# Probe4RackV1_1.net
KiCad netlist of a schematic drawn in Altium Designer
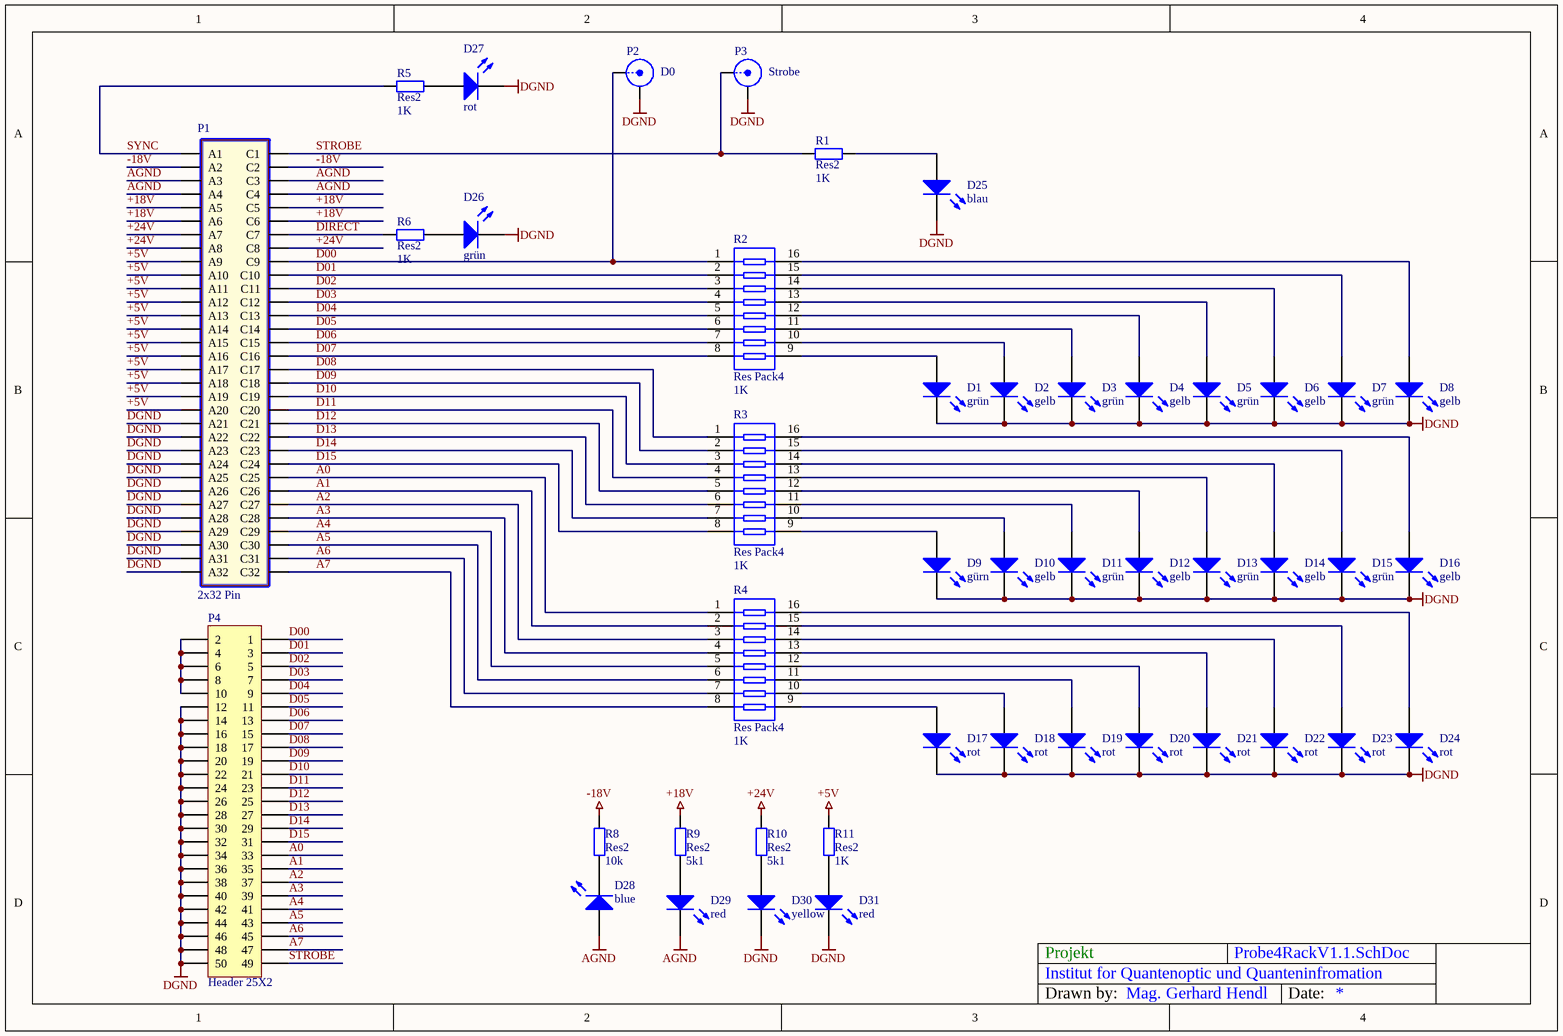
[diagram p0: Probe4RackV1.1.SchDoc]

(export (version "E")
  (design (tool "Eeschema 10.0.6"))
  (components
    (comp (ref "D1")
      (value "grün")
      (footprint "3.2X1.6X1.1")
      (description "Typical BLUE SiC LED")
      (fields (field (name "PUBLISHER") "Altium Limited"))
      (libsource (lib "Miscellaneous Devices") (part "LED3"))
    )
    (comp (ref "D2")
      (value "gelb")
      (footprint "3.2X1.6X1.1")
      (description "Typical BLUE SiC LED")
      (fields (field (name "PUBLISHER") "Altium Limited"))
      (libsource (lib "Miscellaneous Devices") (part "LED3"))
    )
    (comp (ref "D3")
      (value "grün")
      (footprint "3.2X1.6X1.1")
      (description "Typical BLUE SiC LED")
      (fields (field (name "PUBLISHER") "Altium Limited"))
      (libsource (lib "Miscellaneous Devices") (part "LED3"))
    )
    (comp (ref "D4")
      (value "gelb")
      (footprint "3.2X1.6X1.1")
      (description "Typical BLUE SiC LED")
      (fields (field (name "PUBLISHER") "Altium Limited"))
      (libsource (lib "Miscellaneous Devices") (part "LED3"))
    )
    (comp (ref "D5")
      (value "grün")
      (footprint "3.2X1.6X1.1")
      (description "Typical BLUE SiC LED")
      (fields (field (name "PUBLISHER") "Altium Limited"))
      (libsource (lib "Miscellaneous Devices") (part "LED3"))
    )
    (comp (ref "D6")
      (value "gelb")
      (footprint "3.2X1.6X1.1")
      (description "Typical BLUE SiC LED")
      (fields (field (name "PUBLISHER") "Altium Limited"))
      (libsource (lib "Miscellaneous Devices") (part "LED3"))
    )
    (comp (ref "D7")
      (value "grün")
      (footprint "3.2X1.6X1.1")
      (description "Typical BLUE SiC LED")
      (fields (field (name "PUBLISHER") "Altium Limited"))
      (libsource (lib "Miscellaneous Devices") (part "LED3"))
    )
    (comp (ref "D8")
      (value "gelb")
      (footprint "3.2X1.6X1.1")
      (description "Typical BLUE SiC LED")
      (fields (field (name "PUBLISHER") "Altium Limited"))
      (libsource (lib "Miscellaneous Devices") (part "LED3"))
    )
    (comp (ref "D9")
      (value "gürn")
      (footprint "3.2X1.6X1.1")
      (description "Typical BLUE SiC LED")
      (fields (field (name "PUBLISHER") "Altium Limited"))
      (libsource (lib "Miscellaneous Devices") (part "LED3"))
    )
    (comp (ref "D10")
      (value "gelb")
      (footprint "3.2X1.6X1.1")
      (description "Typical BLUE SiC LED")
      (fields (field (name "PUBLISHER") "Altium Limited"))
      (libsource (lib "Miscellaneous Devices") (part "LED3"))
    )
    (comp (ref "D11")
      (value "grün")
      (footprint "3.2X1.6X1.1")
      (description "Typical BLUE SiC LED")
      (fields (field (name "PUBLISHER") "Altium Limited"))
      (libsource (lib "Miscellaneous Devices") (part "LED3"))
    )
    (comp (ref "D12")
      (value "gelb")
      (footprint "3.2X1.6X1.1")
      (description "Typical BLUE SiC LED")
      (fields (field (name "PUBLISHER") "Altium Limited"))
      (libsource (lib "Miscellaneous Devices") (part "LED3"))
    )
    (comp (ref "D13")
      (value "grün")
      (footprint "3.2X1.6X1.1")
      (description "Typical BLUE SiC LED")
      (fields (field (name "PUBLISHER") "Altium Limited"))
      (libsource (lib "Miscellaneous Devices") (part "LED3"))
    )
    (comp (ref "D14")
      (value "gelb")
      (footprint "3.2X1.6X1.1")
      (description "Typical BLUE SiC LED")
      (fields (field (name "PUBLISHER") "Altium Limited"))
      (libsource (lib "Miscellaneous Devices") (part "LED3"))
    )
    (comp (ref "D15")
      (value "grün")
      (footprint "3.2X1.6X1.1")
      (description "Typical BLUE SiC LED")
      (fields (field (name "PUBLISHER") "Altium Limited"))
      (libsource (lib "Miscellaneous Devices") (part "LED3"))
    )
    (comp (ref "D16")
      (value "gelb")
      (footprint "3.2X1.6X1.1")
      (description "Typical BLUE SiC LED")
      (fields (field (name "PUBLISHER") "Altium Limited"))
      (libsource (lib "Miscellaneous Devices") (part "LED3"))
    )
    (comp (ref "D17")
      (value "rot")
      (footprint "3.2X1.6X1.1")
      (description "Typical BLUE SiC LED")
      (fields (field (name "PUBLISHER") "Altium Limited"))
      (libsource (lib "Miscellaneous Devices") (part "LED3"))
    )
    (comp (ref "D18")
      (value "rot")
      (footprint "3.2X1.6X1.1")
      (description "Typical BLUE SiC LED")
      (fields (field (name "PUBLISHER") "Altium Limited"))
      (libsource (lib "Miscellaneous Devices") (part "LED3"))
    )
    (comp (ref "D19")
      (value "rot")
      (footprint "3.2X1.6X1.1")
      (description "Typical BLUE SiC LED")
      (fields (field (name "PUBLISHER") "Altium Limited"))
      (libsource (lib "Miscellaneous Devices") (part "LED3"))
    )
    (comp (ref "D20")
      (value "rot")
      (footprint "3.2X1.6X1.1")
      (description "Typical BLUE SiC LED")
      (fields (field (name "PUBLISHER") "Altium Limited"))
      (libsource (lib "Miscellaneous Devices") (part "LED3"))
    )
    (comp (ref "D21")
      (value "rot")
      (footprint "3.2X1.6X1.1")
      (description "Typical BLUE SiC LED")
      (fields (field (name "PUBLISHER") "Altium Limited"))
      (libsource (lib "Miscellaneous Devices") (part "LED3"))
    )
    (comp (ref "D22")
      (value "rot")
      (footprint "3.2X1.6X1.1")
      (description "Typical BLUE SiC LED")
      (fields (field (name "PUBLISHER") "Altium Limited"))
      (libsource (lib "Miscellaneous Devices") (part "LED3"))
    )
    (comp (ref "D23")
      (value "rot")
      (footprint "3.2X1.6X1.1")
      (description "Typical BLUE SiC LED")
      (fields (field (name "PUBLISHER") "Altium Limited"))
      (libsource (lib "Miscellaneous Devices") (part "LED3"))
    )
    (comp (ref "D24")
      (value "rot")
      (footprint "3.2X1.6X1.1")
      (description "Typical BLUE SiC LED")
      (fields (field (name "PUBLISHER") "Altium Limited"))
      (libsource (lib "Miscellaneous Devices") (part "LED3"))
    )
    (comp (ref "D25")
      (value "blau")
      (footprint "3.2X1.6X1.1")
      (description "Typical BLUE SiC LED")
      (fields (field (name "PUBLISHER") "Altium Limited"))
      (libsource (lib "Miscellaneous Devices") (part "LED3"))
    )
    (comp (ref "D26")
      (value "grün")
      (footprint "3.2X1.6X1.1")
      (description "Typical BLUE SiC LED")
      (fields (field (name "PUBLISHER") "Altium Limited"))
      (libsource (lib "Miscellaneous Devices") (part "LED3"))
    )
    (comp (ref "D27")
      (value "rot")
      (footprint "3.2X1.6X1.1")
      (description "Typical BLUE SiC LED")
      (fields (field (name "PUBLISHER") "Altium Limited"))
      (libsource (lib "Miscellaneous Devices") (part "LED3"))
    )
    (comp (ref "D28")
      (value "blue")
      (footprint "3.2X1.6X1.1")
      (description "Typical BLUE SiC LED")
      (fields (field (name "PUBLISHER") "Altium Limited"))
      (libsource (lib "Miscellaneous Devices") (part "LED3"))
    )
    (comp (ref "D29")
      (value "red")
      (footprint "3.2X1.6X1.1")
      (description "Typical BLUE SiC LED")
      (fields (field (name "PUBLISHER") "Altium Limited"))
      (libsource (lib "Miscellaneous Devices") (part "LED3"))
    )
    (comp (ref "D30")
      (value "yellow")
      (footprint "3.2X1.6X1.1")
      (description "Typical BLUE SiC LED")
      (fields (field (name "PUBLISHER") "Altium Limited"))
      (libsource (lib "Miscellaneous Devices") (part "LED3"))
    )
    (comp (ref "D31")
      (value "red")
      (footprint "3.2X1.6X1.1")
      (description "Typical BLUE SiC LED")
      (fields (field (name "PUBLISHER") "Altium Limited"))
      (libsource (lib "Miscellaneous Devices") (part "LED3"))
    )
    (comp (ref "P1")
      (value "2x32 Pin")
      (footprint "0903164X919")
      (description "DIN 41612")
      (libsource (lib "GeneralParts") (part "64 Pin Header"))
    )
    (comp (ref "P2")
      (value "D0")
      (footprint "BNC_RA CON")
      (description "BNC Elbow Connector")
      (fields (field (name "PUBLISHER") "Altium Limited"))
      (libsource (lib "Miscellaneous Connectors") (part "BNC"))
    )
    (comp (ref "P3")
      (value "Strobe")
      (footprint "BNC_RA CON")
      (description "BNC Elbow Connector")
      (fields (field (name "PUBLISHER") "Altium Limited"))
      (libsource (lib "Miscellaneous Connectors") (part "BNC"))
    )
    (comp (ref "P4")
      (value "Header 25X2")
      (footprint "HDR2X25")
      (description "Header, 25-Pin, Dual row")
      (fields (field (name "PUBLISHER") "Altium Limited"))
      (libsource (lib "Miscellaneous Connectors") (part "Header 25X2"))
    )
    (comp (ref "R1")
      (value "Res2")
      (footprint "RESC3216M")
      (description "Resistor")
      (fields (field (name "ALTIUM_VALUE") "1K") (field (name "PUBLISHER") "Altium Limited"))
      (libsource (lib "Miscellaneous Devices") (part "Res2"))
    )
    (comp (ref "R2")
      (value "Res Pack4")
      (footprint "smd16")
      (description "Isolated Resistor Network")
      (fields (field (name "ALTIUM_VALUE") "1K") (field (name "PUBLISHER") "Altium Limited"))
      (libsource (lib "Miscellaneous Devices") (part "Res Pack4"))
    )
    (comp (ref "R3")
      (value "Res Pack4")
      (footprint "smd16")
      (description "Isolated Resistor Network")
      (fields (field (name "ALTIUM_VALUE") "1K") (field (name "PUBLISHER") "Altium Limited"))
      (libsource (lib "Miscellaneous Devices") (part "Res Pack4"))
    )
    (comp (ref "R4")
      (value "Res Pack4")
      (footprint "smd16")
      (description "Isolated Resistor Network")
      (fields (field (name "ALTIUM_VALUE") "1K") (field (name "PUBLISHER") "Altium Limited"))
      (libsource (lib "Miscellaneous Devices") (part "Res Pack4"))
    )
    (comp (ref "R5")
      (value "Res2")
      (footprint "RESC3216M")
      (description "Resistor")
      (fields (field (name "ALTIUM_VALUE") "1K") (field (name "PUBLISHER") "Altium Limited"))
      (libsource (lib "") (part "Res2_2"))
    )
    (comp (ref "R6")
      (value "Res2")
      (footprint "RESC3216M")
      (description "Resistor")
      (fields (field (name "ALTIUM_VALUE") "1K") (field (name "PUBLISHER") "Altium Limited"))
      (libsource (lib "Miscellaneous Devices") (part "Res2"))
    )
    (comp (ref "R8")
      (value "Res2")
      (footprint "RESC3216M")
      (description "Resistor")
      (fields (field (name "ALTIUM_VALUE") "10k") (field (name "PUBLISHER") "Altium Limited"))
      (libsource (lib "") (part "Res2_1"))
    )
    (comp (ref "R9")
      (value "Res2")
      (footprint "RESC3216M")
      (description "Resistor")
      (fields (field (name "ALTIUM_VALUE") "5k1") (field (name "PUBLISHER") "Altium Limited"))
      (libsource (lib "") (part "Res2_1"))
    )
    (comp (ref "R10")
      (value "Res2")
      (footprint "RESC3216M")
      (description "Resistor")
      (fields (field (name "ALTIUM_VALUE") "5k1") (field (name "PUBLISHER") "Altium Limited"))
      (libsource (lib "") (part "Res2_1"))
    )
    (comp (ref "R11")
      (value "Res2")
      (footprint "RESC3216M")
      (description "Resistor")
      (fields (field (name "ALTIUM_VALUE") "1K") (field (name "PUBLISHER") "Altium Limited"))
      (libsource (lib "") (part "Res2_1"))
    )
  )
  (nets
    (net (code "1") (name "+5V") (class "Default")
      (node (ref "P1") (pin "A10") (pinfunction "A10_A10") (pintype "passive"))
      (node (ref "P1") (pin "A11") (pinfunction "A11_A11") (pintype "passive"))
      (node (ref "P1") (pin "A12") (pinfunction "A12_A12") (pintype "passive"))
      (node (ref "P1") (pin "A13") (pinfunction "A13_A13") (pintype "passive"))
      (node (ref "P1") (pin "A14") (pinfunction "A14_A14") (pintype "passive"))
      (node (ref "P1") (pin "A15") (pinfunction "A15_A15") (pintype "passive"))
      (node (ref "P1") (pin "A16") (pinfunction "A16_A16") (pintype "passive"))
      (node (ref "P1") (pin "A17") (pinfunction "A17_A17") (pintype "passive"))
      (node (ref "P1") (pin "A18") (pinfunction "A18_A18") (pintype "passive"))
      (node (ref "P1") (pin "A19") (pinfunction "A19_A19") (pintype "passive"))
      (node (ref "P1") (pin "A20") (pinfunction "A20_A20") (pintype "passive"))
      (node (ref "P1") (pin "A9") (pinfunction "A9_A9") (pintype "passive"))
      (node (ref "R11") (pin "1") (pinfunction "1_1") (pintype "passive"))
    )
    (net (code "2") (name "+18V") (class "Default")
      (node (ref "P1") (pin "A5") (pinfunction "A5_A5") (pintype "passive"))
      (node (ref "P1") (pin "A6") (pinfunction "A6_A6") (pintype "passive"))
      (node (ref "P1") (pin "C5") (pinfunction "C5_C5") (pintype "passive"))
      (node (ref "P1") (pin "C6") (pinfunction "C6_C6") (pintype "passive"))
      (node (ref "R9") (pin "1") (pinfunction "1_1") (pintype "passive"))
    )
    (net (code "3") (name "+24V") (class "Default")
      (node (ref "P1") (pin "A7") (pinfunction "A7_A7") (pintype "passive"))
      (node (ref "P1") (pin "A8") (pinfunction "A8_A8") (pintype "passive"))
      (node (ref "P1") (pin "C8") (pinfunction "C8_C8") (pintype "passive"))
      (node (ref "R10") (pin "1") (pinfunction "1_1") (pintype "passive"))
    )
    (net (code "4") (name "-18V") (class "Default")
      (node (ref "P1") (pin "A2") (pinfunction "A2_A2") (pintype "passive"))
      (node (ref "P1") (pin "C2") (pinfunction "C2_C2") (pintype "passive"))
      (node (ref "R8") (pin "1") (pinfunction "1_1") (pintype "passive"))
    )
    (net (code "5") (name "/A0") (class "Default")
      (node (ref "P1") (pin "C25") (pinfunction "C25_C25") (pintype "passive"))
      (node (ref "P4") (pin "33") (pinfunction "33_33") (pintype "passive"))
      (node (ref "R4") (pin "1") (pinfunction "1_1") (pintype "passive"))
    )
    (net (code "6") (name "/A1") (class "Default")
      (node (ref "P1") (pin "C26") (pinfunction "C26_C26") (pintype "passive"))
      (node (ref "P4") (pin "35") (pinfunction "35_35") (pintype "passive"))
      (node (ref "R4") (pin "2") (pinfunction "2_2") (pintype "passive"))
    )
    (net (code "7") (name "/A2") (class "Default")
      (node (ref "P1") (pin "C27") (pinfunction "C27_C27") (pintype "passive"))
      (node (ref "P4") (pin "37") (pinfunction "37_37") (pintype "passive"))
      (node (ref "R4") (pin "3") (pinfunction "3_3") (pintype "passive"))
    )
    (net (code "8") (name "/A3") (class "Default")
      (node (ref "P1") (pin "C28") (pinfunction "C28_C28") (pintype "passive"))
      (node (ref "P4") (pin "39") (pinfunction "39_39") (pintype "passive"))
      (node (ref "R4") (pin "4") (pinfunction "4_4") (pintype "passive"))
    )
    (net (code "9") (name "/A4") (class "Default")
      (node (ref "P1") (pin "C29") (pinfunction "C29_C29") (pintype "passive"))
      (node (ref "P4") (pin "41") (pinfunction "41_41") (pintype "passive"))
      (node (ref "R4") (pin "5") (pinfunction "5_5") (pintype "passive"))
    )
    (net (code "10") (name "/A5") (class "Default")
      (node (ref "P1") (pin "C30") (pinfunction "C30_C30") (pintype "passive"))
      (node (ref "P4") (pin "43") (pinfunction "43_43") (pintype "passive"))
      (node (ref "R4") (pin "6") (pinfunction "6_6") (pintype "passive"))
    )
    (net (code "11") (name "/A6") (class "Default")
      (node (ref "P1") (pin "C31") (pinfunction "C31_C31") (pintype "passive"))
      (node (ref "P4") (pin "45") (pinfunction "45_45") (pintype "passive"))
      (node (ref "R4") (pin "7") (pinfunction "7_7") (pintype "passive"))
    )
    (net (code "12") (name "/A7") (class "Default")
      (node (ref "P1") (pin "C32") (pinfunction "C32_C32") (pintype "passive"))
      (node (ref "P4") (pin "47") (pinfunction "47_47") (pintype "passive"))
      (node (ref "R4") (pin "8") (pinfunction "8_8") (pintype "passive"))
    )
    (net (code "13") (name "/D00") (class "Default")
      (node (ref "P1") (pin "C9") (pinfunction "C9_C9") (pintype "passive"))
      (node (ref "P2") (pin "1") (pinfunction "X_1") (pintype "passive"))
      (node (ref "P4") (pin "1") (pinfunction "1_1") (pintype "passive"))
      (node (ref "R2") (pin "1") (pinfunction "1_1") (pintype "passive"))
    )
    (net (code "14") (name "/D01") (class "Default")
      (node (ref "P1") (pin "C10") (pinfunction "C10_C10") (pintype "passive"))
      (node (ref "P4") (pin "3") (pinfunction "3_3") (pintype "passive"))
      (node (ref "R2") (pin "2") (pinfunction "2_2") (pintype "passive"))
    )
    (net (code "15") (name "/D02") (class "Default")
      (node (ref "P1") (pin "C11") (pinfunction "C11_C11") (pintype "passive"))
      (node (ref "P4") (pin "5") (pinfunction "5_5") (pintype "passive"))
      (node (ref "R2") (pin "3") (pinfunction "3_3") (pintype "passive"))
    )
    (net (code "16") (name "/D03") (class "Default")
      (node (ref "P1") (pin "C12") (pinfunction "C12_C12") (pintype "passive"))
      (node (ref "P4") (pin "7") (pinfunction "7_7") (pintype "passive"))
      (node (ref "R2") (pin "4") (pinfunction "4_4") (pintype "passive"))
    )
    (net (code "17") (name "/D04") (class "Default")
      (node (ref "P1") (pin "C13") (pinfunction "C13_C13") (pintype "passive"))
      (node (ref "P4") (pin "9") (pinfunction "9_9") (pintype "passive"))
      (node (ref "R2") (pin "5") (pinfunction "5_5") (pintype "passive"))
    )
    (net (code "18") (name "/D05") (class "Default")
      (node (ref "P1") (pin "C14") (pinfunction "C14_C14") (pintype "passive"))
      (node (ref "P4") (pin "11") (pinfunction "11_11") (pintype "passive"))
      (node (ref "R2") (pin "6") (pinfunction "6_6") (pintype "passive"))
    )
    (net (code "19") (name "/D06") (class "Default")
      (node (ref "P1") (pin "C15") (pinfunction "C15_C15") (pintype "passive"))
      (node (ref "P4") (pin "13") (pinfunction "13_13") (pintype "passive"))
      (node (ref "R2") (pin "7") (pinfunction "7_7") (pintype "passive"))
    )
    (net (code "20") (name "/D07") (class "Default")
      (node (ref "P1") (pin "C16") (pinfunction "C16_C16") (pintype "passive"))
      (node (ref "P4") (pin "15") (pinfunction "15_15") (pintype "passive"))
      (node (ref "R2") (pin "8") (pinfunction "8_8") (pintype "passive"))
    )
    (net (code "21") (name "/D08") (class "Default")
      (node (ref "P1") (pin "C17") (pinfunction "C17_C17") (pintype "passive"))
      (node (ref "P4") (pin "17") (pinfunction "17_17") (pintype "passive"))
      (node (ref "R3") (pin "1") (pinfunction "1_1") (pintype "passive"))
    )
    (net (code "22") (name "/D09") (class "Default")
      (node (ref "P1") (pin "C18") (pinfunction "C18_C18") (pintype "passive"))
      (node (ref "P4") (pin "19") (pinfunction "19_19") (pintype "passive"))
      (node (ref "R3") (pin "2") (pinfunction "2_2") (pintype "passive"))
    )
    (net (code "23") (name "/D10") (class "Default")
      (node (ref "P1") (pin "C19") (pinfunction "C19_C19") (pintype "passive"))
      (node (ref "P4") (pin "21") (pinfunction "21_21") (pintype "passive"))
      (node (ref "R3") (pin "3") (pinfunction "3_3") (pintype "passive"))
    )
    (net (code "24") (name "/D11") (class "Default")
      (node (ref "P1") (pin "C20") (pinfunction "C20_C20") (pintype "passive"))
      (node (ref "P4") (pin "23") (pinfunction "23_23") (pintype "passive"))
      (node (ref "R3") (pin "4") (pinfunction "4_4") (pintype "passive"))
    )
    (net (code "25") (name "/D12") (class "Default")
      (node (ref "P1") (pin "C21") (pinfunction "C21_C21") (pintype "passive"))
      (node (ref "P4") (pin "25") (pinfunction "25_25") (pintype "passive"))
      (node (ref "R3") (pin "5") (pinfunction "5_5") (pintype "passive"))
    )
    (net (code "26") (name "/D13") (class "Default")
      (node (ref "P1") (pin "C22") (pinfunction "C22_C22") (pintype "passive"))
      (node (ref "P4") (pin "27") (pinfunction "27_27") (pintype "passive"))
      (node (ref "R3") (pin "6") (pinfunction "6_6") (pintype "passive"))
    )
    (net (code "27") (name "/D14") (class "Default")
      (node (ref "P1") (pin "C23") (pinfunction "C23_C23") (pintype "passive"))
      (node (ref "P4") (pin "29") (pinfunction "29_29") (pintype "passive"))
      (node (ref "R3") (pin "7") (pinfunction "7_7") (pintype "passive"))
    )
    (net (code "28") (name "/D15") (class "Default")
      (node (ref "P1") (pin "C24") (pinfunction "C24_C24") (pintype "passive"))
      (node (ref "P4") (pin "31") (pinfunction "31_31") (pintype "passive"))
      (node (ref "R3") (pin "8") (pinfunction "8_8") (pintype "passive"))
    )
    (net (code "29") (name "/DIRECT") (class "Default")
      (node (ref "P1") (pin "C7") (pinfunction "C7_C7") (pintype "passive"))
      (node (ref "R6") (pin "1") (pinfunction "1_1") (pintype "passive"))
    )
    (net (code "30") (name "/STROBE") (class "Default")
      (node (ref "P1") (pin "C1") (pinfunction "C1_C1") (pintype "passive"))
      (node (ref "P3") (pin "1") (pinfunction "X_1") (pintype "passive"))
      (node (ref "P4") (pin "49") (pinfunction "49_49") (pintype "passive"))
      (node (ref "R1") (pin "1") (pinfunction "1_1") (pintype "passive"))
    )
    (net (code "31") (name "/SYNC") (class "Default")
      (node (ref "P1") (pin "A1") (pinfunction "A1_A1") (pintype "passive"))
      (node (ref "R5") (pin "2") (pinfunction "2_2") (pintype "passive"))
    )
    (net (code "32") (name "AGND") (class "Default")
      (node (ref "D28") (pin "1") (pinfunction "A_1") (pintype "passive"))
      (node (ref "D29") (pin "2") (pinfunction "K_2") (pintype "passive"))
      (node (ref "P1") (pin "A3") (pinfunction "A3_A3") (pintype "passive"))
      (node (ref "P1") (pin "A4") (pinfunction "A4_A4") (pintype "passive"))
      (node (ref "P1") (pin "C3") (pinfunction "C3_C3") (pintype "passive"))
      (node (ref "P1") (pin "C4") (pinfunction "C4_C4") (pintype "passive"))
    )
    (net (code "33") (name "DGND") (class "Default")
      (node (ref "D1") (pin "2") (pinfunction "K_2") (pintype "passive"))
      (node (ref "D10") (pin "2") (pinfunction "K_2") (pintype "passive"))
      (node (ref "D11") (pin "2") (pinfunction "K_2") (pintype "passive"))
      (node (ref "D12") (pin "2") (pinfunction "K_2") (pintype "passive"))
      (node (ref "D13") (pin "2") (pinfunction "K_2") (pintype "passive"))
      (node (ref "D14") (pin "2") (pinfunction "K_2") (pintype "passive"))
      (node (ref "D15") (pin "2") (pinfunction "K_2") (pintype "passive"))
      (node (ref "D16") (pin "2") (pinfunction "K_2") (pintype "passive"))
      (node (ref "D17") (pin "2") (pinfunction "K_2") (pintype "passive"))
      (node (ref "D18") (pin "2") (pinfunction "K_2") (pintype "passive"))
      (node (ref "D19") (pin "2") (pinfunction "K_2") (pintype "passive"))
      (node (ref "D2") (pin "2") (pinfunction "K_2") (pintype "passive"))
      (node (ref "D20") (pin "2") (pinfunction "K_2") (pintype "passive"))
      (node (ref "D21") (pin "2") (pinfunction "K_2") (pintype "passive"))
      (node (ref "D22") (pin "2") (pinfunction "K_2") (pintype "passive"))
      (node (ref "D23") (pin "2") (pinfunction "K_2") (pintype "passive"))
      (node (ref "D24") (pin "2") (pinfunction "K_2") (pintype "passive"))
      (node (ref "D25") (pin "2") (pinfunction "K_2") (pintype "passive"))
      (node (ref "D26") (pin "2") (pinfunction "K_2") (pintype "passive"))
      (node (ref "D27") (pin "2") (pinfunction "K_2") (pintype "passive"))
      (node (ref "D3") (pin "2") (pinfunction "K_2") (pintype "passive"))
      (node (ref "D30") (pin "2") (pinfunction "K_2") (pintype "passive"))
      (node (ref "D31") (pin "2") (pinfunction "K_2") (pintype "passive"))
      (node (ref "D4") (pin "2") (pinfunction "K_2") (pintype "passive"))
      (node (ref "D5") (pin "2") (pinfunction "K_2") (pintype "passive"))
      (node (ref "D6") (pin "2") (pinfunction "K_2") (pintype "passive"))
      (node (ref "D7") (pin "2") (pinfunction "K_2") (pintype "passive"))
      (node (ref "D8") (pin "2") (pinfunction "K_2") (pintype "passive"))
      (node (ref "D9") (pin "2") (pinfunction "K_2") (pintype "passive"))
      (node (ref "P1") (pin "A21") (pinfunction "A21_A21") (pintype "passive"))
      (node (ref "P1") (pin "A22") (pinfunction "A22_A22") (pintype "passive"))
      (node (ref "P1") (pin "A23") (pinfunction "A23_A23") (pintype "passive"))
      (node (ref "P1") (pin "A24") (pinfunction "A24_A24") (pintype "passive"))
      (node (ref "P1") (pin "A25") (pinfunction "A25_A25") (pintype "passive"))
      (node (ref "P1") (pin "A26") (pinfunction "A26_A26") (pintype "passive"))
      (node (ref "P1") (pin "A27") (pinfunction "A27_A27") (pintype "passive"))
      (node (ref "P1") (pin "A28") (pinfunction "A28_A28") (pintype "passive"))
      (node (ref "P1") (pin "A29") (pinfunction "A29_A29") (pintype "passive"))
      (node (ref "P1") (pin "A30") (pinfunction "A30_A30") (pintype "passive"))
      (node (ref "P1") (pin "A31") (pinfunction "A31_A31") (pintype "passive"))
      (node (ref "P1") (pin "A32") (pinfunction "A32_A32") (pintype "passive"))
      (node (ref "P2") (pin "2") (pinfunction "Y_2") (pintype "passive"))
      (node (ref "P3") (pin "2") (pinfunction "Y_2") (pintype "passive"))
      (node (ref "P4") (pin "12") (pinfunction "12_12") (pintype "passive"))
      (node (ref "P4") (pin "14") (pinfunction "14_14") (pintype "passive"))
      (node (ref "P4") (pin "16") (pinfunction "16_16") (pintype "passive"))
      (node (ref "P4") (pin "18") (pinfunction "18_18") (pintype "passive"))
      (node (ref "P4") (pin "20") (pinfunction "20_20") (pintype "passive"))
      (node (ref "P4") (pin "22") (pinfunction "22_22") (pintype "passive"))
      (node (ref "P4") (pin "24") (pinfunction "24_24") (pintype "passive"))
      (node (ref "P4") (pin "26") (pinfunction "26_26") (pintype "passive"))
      (node (ref "P4") (pin "28") (pinfunction "28_28") (pintype "passive"))
      (node (ref "P4") (pin "30") (pinfunction "30_30") (pintype "passive"))
      (node (ref "P4") (pin "32") (pinfunction "32_32") (pintype "passive"))
      (node (ref "P4") (pin "34") (pinfunction "34_34") (pintype "passive"))
      (node (ref "P4") (pin "36") (pinfunction "36_36") (pintype "passive"))
      (node (ref "P4") (pin "38") (pinfunction "38_38") (pintype "passive"))
      (node (ref "P4") (pin "40") (pinfunction "40_40") (pintype "passive"))
      (node (ref "P4") (pin "42") (pinfunction "42_42") (pintype "passive"))
      (node (ref "P4") (pin "44") (pinfunction "44_44") (pintype "passive"))
      (node (ref "P4") (pin "46") (pinfunction "46_46") (pintype "passive"))
      (node (ref "P4") (pin "48") (pinfunction "48_48") (pintype "passive"))
      (node (ref "P4") (pin "50") (pinfunction "50_50") (pintype "passive"))
    )
    (net (code "34") (name "Net-(D1-A)") (class "Default")
      (node (ref "D1") (pin "1") (pinfunction "A_1") (pintype "passive"))
      (node (ref "R2") (pin "9") (pinfunction "9_9") (pintype "passive"))
    )
    (net (code "35") (name "Net-(D2-A)") (class "Default")
      (node (ref "D2") (pin "1") (pinfunction "A_1") (pintype "passive"))
      (node (ref "R2") (pin "10") (pinfunction "10_10") (pintype "passive"))
    )
    (net (code "36") (name "Net-(D3-A)") (class "Default")
      (node (ref "D3") (pin "1") (pinfunction "A_1") (pintype "passive"))
      (node (ref "R2") (pin "11") (pinfunction "11_11") (pintype "passive"))
    )
    (net (code "37") (name "Net-(D4-A)") (class "Default")
      (node (ref "D4") (pin "1") (pinfunction "A_1") (pintype "passive"))
      (node (ref "R2") (pin "12") (pinfunction "12_12") (pintype "passive"))
    )
    (net (code "38") (name "Net-(D5-A)") (class "Default")
      (node (ref "D5") (pin "1") (pinfunction "A_1") (pintype "passive"))
      (node (ref "R2") (pin "13") (pinfunction "13_13") (pintype "passive"))
    )
    (net (code "39") (name "Net-(D6-A)") (class "Default")
      (node (ref "D6") (pin "1") (pinfunction "A_1") (pintype "passive"))
      (node (ref "R2") (pin "14") (pinfunction "14_14") (pintype "passive"))
    )
    (net (code "40") (name "Net-(D7-A)") (class "Default")
      (node (ref "D7") (pin "1") (pinfunction "A_1") (pintype "passive"))
      (node (ref "R2") (pin "15") (pinfunction "15_15") (pintype "passive"))
    )
    (net (code "41") (name "Net-(D8-A)") (class "Default")
      (node (ref "D8") (pin "1") (pinfunction "A_1") (pintype "passive"))
      (node (ref "R2") (pin "16") (pinfunction "16_16") (pintype "passive"))
    )
    (net (code "42") (name "Net-(D9-A)") (class "Default")
      (node (ref "D9") (pin "1") (pinfunction "A_1") (pintype "passive"))
      (node (ref "R3") (pin "9") (pinfunction "9_9") (pintype "passive"))
    )
    (net (code "43") (name "Net-(D10-A)") (class "Default")
      (node (ref "D10") (pin "1") (pinfunction "A_1") (pintype "passive"))
      (node (ref "R3") (pin "10") (pinfunction "10_10") (pintype "passive"))
    )
    (net (code "44") (name "Net-(D11-A)") (class "Default")
      (node (ref "D11") (pin "1") (pinfunction "A_1") (pintype "passive"))
      (node (ref "R3") (pin "11") (pinfunction "11_11") (pintype "passive"))
    )
    (net (code "45") (name "Net-(D12-A)") (class "Default")
      (node (ref "D12") (pin "1") (pinfunction "A_1") (pintype "passive"))
      (node (ref "R3") (pin "12") (pinfunction "12_12") (pintype "passive"))
    )
    (net (code "46") (name "Net-(D13-A)") (class "Default")
      (node (ref "D13") (pin "1") (pinfunction "A_1") (pintype "passive"))
      (node (ref "R3") (pin "13") (pinfunction "13_13") (pintype "passive"))
    )
    (net (code "47") (name "Net-(D14-A)") (class "Default")
      (node (ref "D14") (pin "1") (pinfunction "A_1") (pintype "passive"))
      (node (ref "R3") (pin "14") (pinfunction "14_14") (pintype "passive"))
    )
    (net (code "48") (name "Net-(D15-A)") (class "Default")
      (node (ref "D15") (pin "1") (pinfunction "A_1") (pintype "passive"))
      (node (ref "R3") (pin "15") (pinfunction "15_15") (pintype "passive"))
    )
    (net (code "49") (name "Net-(D16-A)") (class "Default")
      (node (ref "D16") (pin "1") (pinfunction "A_1") (pintype "passive"))
      (node (ref "R3") (pin "16") (pinfunction "16_16") (pintype "passive"))
    )
    (net (code "50") (name "Net-(D17-A)") (class "Default")
      (node (ref "D17") (pin "1") (pinfunction "A_1") (pintype "passive"))
      (node (ref "R4") (pin "9") (pinfunction "9_9") (pintype "passive"))
    )
    (net (code "51") (name "Net-(D18-A)") (class "Default")
      (node (ref "D18") (pin "1") (pinfunction "A_1") (pintype "passive"))
      (node (ref "R4") (pin "10") (pinfunction "10_10") (pintype "passive"))
    )
    (net (code "52") (name "Net-(D19-A)") (class "Default")
      (node (ref "D19") (pin "1") (pinfunction "A_1") (pintype "passive"))
      (node (ref "R4") (pin "11") (pinfunction "11_11") (pintype "passive"))
    )
    (net (code "53") (name "Net-(D20-A)") (class "Default")
      (node (ref "D20") (pin "1") (pinfunction "A_1") (pintype "passive"))
      (node (ref "R4") (pin "12") (pinfunction "12_12") (pintype "passive"))
    )
    (net (code "54") (name "Net-(D21-A)") (class "Default")
      (node (ref "D21") (pin "1") (pinfunction "A_1") (pintype "passive"))
      (node (ref "R4") (pin "13") (pinfunction "13_13") (pintype "passive"))
    )
    (net (code "55") (name "Net-(D22-A)") (class "Default")
      (node (ref "D22") (pin "1") (pinfunction "A_1") (pintype "passive"))
      (node (ref "R4") (pin "14") (pinfunction "14_14") (pintype "passive"))
    )
    (net (code "56") (name "Net-(D23-A)") (class "Default")
      (node (ref "D23") (pin "1") (pinfunction "A_1") (pintype "passive"))
      (node (ref "R4") (pin "15") (pinfunction "15_15") (pintype "passive"))
    )
    (net (code "57") (name "Net-(D24-A)") (class "Default")
      (node (ref "D24") (pin "1") (pinfunction "A_1") (pintype "passive"))
      (node (ref "R4") (pin "16") (pinfunction "16_16") (pintype "passive"))
    )
    (net (code "58") (name "Net-(D25-A)") (class "Default")
      (node (ref "D25") (pin "1") (pinfunction "A_1") (pintype "passive"))
      (node (ref "R1") (pin "2") (pinfunction "2_2") (pintype "passive"))
    )
    (net (code "59") (name "Net-(D26-A)") (class "Default")
      (node (ref "D26") (pin "1") (pinfunction "A_1") (pintype "passive"))
      (node (ref "R6") (pin "2") (pinfunction "2_2") (pintype "passive"))
    )
    (net (code "60") (name "Net-(D27-A)") (class "Default")
      (node (ref "D27") (pin "1") (pinfunction "A_1") (pintype "passive"))
      (node (ref "R5") (pin "1") (pinfunction "1_1") (pintype "passive"))
    )
    (net (code "61") (name "Net-(D28-K)") (class "Default")
      (node (ref "D28") (pin "2") (pinfunction "K_2") (pintype "passive"))
      (node (ref "R8") (pin "2") (pinfunction "2_2") (pintype "passive"))
    )
    (net (code "62") (name "Net-(D29-A)") (class "Default")
      (node (ref "D29") (pin "1") (pinfunction "A_1") (pintype "passive"))
      (node (ref "R9") (pin "2") (pinfunction "2_2") (pintype "passive"))
    )
    (net (code "63") (name "Net-(D30-A)") (class "Default")
      (node (ref "D30") (pin "1") (pinfunction "A_1") (pintype "passive"))
      (node (ref "R10") (pin "2") (pinfunction "2_2") (pintype "passive"))
    )
    (net (code "64") (name "Net-(D31-A)") (class "Default")
      (node (ref "D31") (pin "1") (pinfunction "A_1") (pintype "passive"))
      (node (ref "R11") (pin "2") (pinfunction "2_2") (pintype "passive"))
    )
    (net (code "65") (name "Net-(P4-Pad10)") (class "Default")
      (node (ref "P4") (pin "10") (pinfunction "10_10") (pintype "passive"))
      (node (ref "P4") (pin "2") (pinfunction "2_2") (pintype "passive"))
      (node (ref "P4") (pin "4") (pinfunction "4_4") (pintype "passive"))
      (node (ref "P4") (pin "6") (pinfunction "6_6") (pintype "passive"))
      (node (ref "P4") (pin "8") (pinfunction "8_8") (pintype "passive"))
    )
  )
)
